# v1_0.net
KiCad netlist of a schematic drawn in Altium Designer
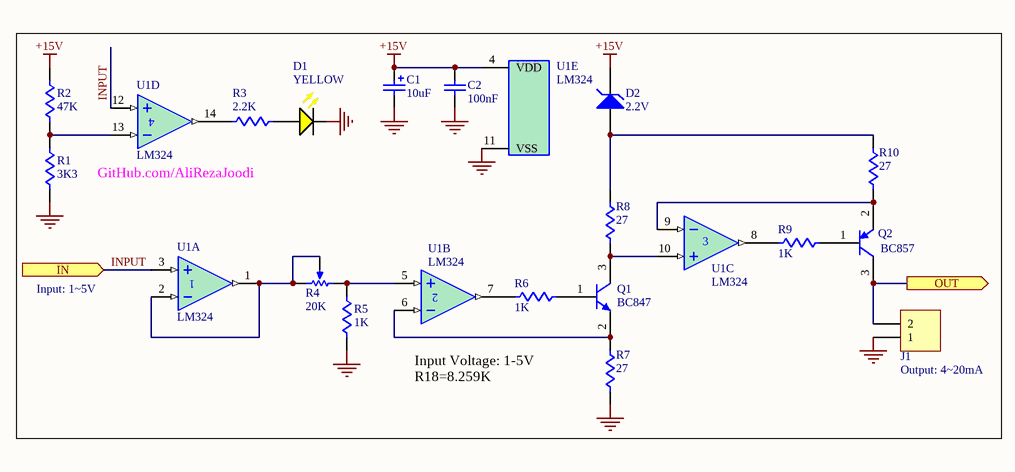
[diagram p0: v1.0.SchDoc]

(export (version "E")
  (design (tool "Eeschema 10.0.6"))
  (components
    (comp (ref "C1")
      (value "10uF")
      (footprint "Cap_B")
      (description "Polarized Capacitor (Radial)")
      (fields
        (field (name "MANUFACTURER") "Generic Components")
        (field (name "Comment") "Capacitor")
        (field (name "PUBLISHER") "Altium Limited")
      )
      (libsource (lib "Miscellaneous Devices") (part "Cap Pol1"))
    )
    (comp (ref "C2")
      (value "100nF")
      (footprint "0805")
      (description "Capacitor")
      (fields
        (field (name "MANUFACTURER") "Generic Components")
        (field (name "Comment") "Cap")
        (field (name "PUBLISHER") "Altium Limited")
      )
      (libsource (lib "Miscellaneous Devices") (part "Cap"))
    )
    (comp (ref "D1")
      (value "YELLOW")
      (footprint "LED_THD_3MM_YELLOW_R")
      (description "LED, Yellow")
      (fields (field (name "MANUFACTURER") "Generic Components") (field (name "PUBLISHER") "Altium Limited"))
      (libsource (lib "Display") (part "LED_YELLOW"))
    )
    (comp (ref "D2")
      (value "2.2V")
      (footprint "MELF-D3516-1406")
      (description "Zener Diode")
      (fields
        (field (name "MANUFACTURER") "Generic Components")
        (field (name "Comment") "LED")
        (field (name "PUBLISHER") "Altium Limited")
      )
      (libsource (lib "Miscellaneous Devices") (part "D Zener"))
    )
    (comp (ref "J1")
      (value "J17")
      (footprint "Fonics_2PIN_1")
      (description "Header, 2-Pin")
      (fields (field (name "PUBLISHER") "Altium Limited"))
      (libsource (lib "Miscellaneous Connectors") (part "Header 2"))
    )
    (comp (ref "Q1")
      (value "BC847")
      (footprint "SOT23-3N")
      (description "Silicon Bipolar Transistor")
      (fields (field (name "Comment") "NPN"))
      (libsource (lib "my Libraries") (part "BC847"))
    )
    (comp (ref "Q2")
      (value "BC857")
      (footprint "SOT23-3N")
      (description "Silicon Bipolar Transistor")
      (fields (field (name "Comment") "Q"))
      (libsource (lib "my Libraries") (part "BC857"))
    )
    (comp (ref "R1")
      (value "3K3")
      (footprint "0805")
      (description "Resistor")
      (fields (field (name "MANUFACTURER") "Generic Components") (field (name "PUBLISHER") "Altium Limited"))
      (libsource (lib "Miscellaneous Devices") (part "Res1"))
    )
    (comp (ref "R2")
      (value "47K")
      (footprint "0805")
      (description "Resistor")
      (fields
        (field (name "MANUFACTURER") "Generic Components")
        (field (name "Comment") "Res")
        (field (name "PUBLISHER") "Altium Limited")
      )
      (libsource (lib "Miscellaneous Devices") (part "Res1"))
    )
    (comp (ref "R3")
      (value "2.2K")
      (footprint "0805")
      (description "Resistor")
      (fields
        (field (name "MANUFACTURER") "Generic Components")
        (field (name "Comment") "Res")
        (field (name "PUBLISHER") "Altium Limited")
      )
      (libsource (lib "Miscellaneous Devices") (part "Res1"))
    )
    (comp (ref "R4")
      (value "20K")
      (footprint "VR4_")
      (description "Potentiometer")
      (fields
        (field (name "MANUFACTURER") "Generic Components")
        (field (name "Comment") "RES")
        (field (name "PUBLISHER") "Altium Limited")
      )
      (libsource (lib "my Libraries") (part "RPot1"))
    )
    (comp (ref "R5")
      (value "1K")
      (footprint "0805")
      (description "Resistor")
      (fields
        (field (name "MANUFACTURER") "Generic Components")
        (field (name "Comment") "RES")
        (field (name "PUBLISHER") "Altium Limited")
      )
      (libsource (lib "Miscellaneous Devices") (part "Res1"))
    )
    (comp (ref "R6")
      (value "1K")
      (footprint "0805")
      (description "Resistor")
      (fields
        (field (name "MANUFACTURER") "Generic Components")
        (field (name "Comment") "RES")
        (field (name "PUBLISHER") "Altium Limited")
      )
      (libsource (lib "Miscellaneous Devices") (part "Res1"))
    )
    (comp (ref "R7")
      (value "27")
      (footprint "0805")
      (description "Resistor")
      (fields
        (field (name "MANUFACTURER") "Generic Components")
        (field (name "Comment") "R59")
        (field (name "PUBLISHER") "Altium Limited")
      )
      (libsource (lib "Miscellaneous Devices") (part "Res1"))
    )
    (comp (ref "R8")
      (value "27")
      (footprint "0805")
      (description "Resistor")
      (fields
        (field (name "MANUFACTURER") "Generic Components")
        (field (name "Comment") "R58")
        (field (name "PUBLISHER") "Altium Limited")
      )
      (libsource (lib "Miscellaneous Devices") (part "Res1"))
    )
    (comp (ref "R9")
      (value "1K")
      (footprint "0805")
      (description "Resistor")
      (fields
        (field (name "MANUFACTURER") "Generic Components")
        (field (name "Comment") "R61")
        (field (name "PUBLISHER") "Altium Limited")
      )
      (libsource (lib "Miscellaneous Devices") (part "Res1"))
    )
    (comp (ref "R10")
      (value "27")
      (footprint "0805")
      (description "Resistor")
      (fields
        (field (name "MANUFACTURER") "Generic Components")
        (field (name "Comment") "R60")
        (field (name "PUBLISHER") "Altium Limited")
      )
      (libsource (lib "Miscellaneous Devices") (part "Res1"))
    )
    (comp (ref "U1")
      (value "LM324")
      (footprint "DIP_14")
      (description "Quad Low-Power Operational Amplifier")
      (fields (field (name "PUBLISHER") "Altium Limited"))
      (libsource (lib "Op-Amp") (part "LM324"))
    )
  )
  (nets
    (net (code "1") (name "+15V") (class "Default")
      (node (ref "C1") (pin "1") (pinfunction "1_1") (pintype "passive"))
      (node (ref "C2") (pin "2") (pinfunction "2_2") (pintype "passive"))
      (node (ref "D2") (pin "2") (pinfunction "K_2") (pintype "passive"))
      (node (ref "R2") (pin "1") (pinfunction "1_1") (pintype "passive"))
      (node (ref "U1") (pin "4") (pinfunction "VDD_4") (pintype "passive"))
    )
    (net (code "2") (name "/INPUT") (class "Default")
      (node (ref "U1") (pin "12") (pinfunction "IN+_12") (pintype "input"))
      (node (ref "U1") (pin "3") (pinfunction "IN+_3") (pintype "input"))
    )
    (net (code "3") (name "/OUT") (class "Default")
      (node (ref "J1") (pin "2") (pinfunction "2_2") (pintype "passive"))
      (node (ref "Q2") (pin "3") (pinfunction "C_3") (pintype "passive"))
    )
    (net (code "4") (name "GND") (class "Default")
      (node (ref "C1") (pin "2") (pinfunction "2_2") (pintype "passive"))
      (node (ref "C2") (pin "1") (pinfunction "1_1") (pintype "passive"))
      (node (ref "D1") (pin "2") (pinfunction "K_2") (pintype "passive"))
      (node (ref "J1") (pin "1") (pinfunction "1_1") (pintype "passive"))
      (node (ref "R1") (pin "2") (pinfunction "2_2") (pintype "passive"))
      (node (ref "R5") (pin "2") (pinfunction "2_2") (pintype "passive"))
      (node (ref "R7") (pin "1") (pinfunction "1_1") (pintype "passive"))
      (node (ref "U1") (pin "11") (pinfunction "VSS_11") (pintype "power_in"))
    )
    (net (code "5") (name "Net-(D1-A)") (class "Default")
      (node (ref "D1") (pin "1") (pinfunction "A_1") (pintype "passive"))
      (node (ref "R3") (pin "1") (pinfunction "1_1") (pintype "passive"))
    )
    (net (code "6") (name "Net-(D2-A)") (class "Default")
      (node (ref "D2") (pin "1") (pinfunction "A_1") (pintype "passive"))
      (node (ref "R10") (pin "2") (pinfunction "2_2") (pintype "passive"))
      (node (ref "R8") (pin "2") (pinfunction "2_2") (pintype "passive"))
    )
    (net (code "7") (name "Net-(Q1-B)") (class "Default")
      (node (ref "Q1") (pin "1") (pinfunction "B_1") (pintype "passive"))
      (node (ref "R6") (pin "2") (pinfunction "2_2") (pintype "passive"))
    )
    (net (code "8") (name "Net-(Q1-C)") (class "Default")
      (node (ref "Q1") (pin "3") (pinfunction "C_3") (pintype "passive"))
      (node (ref "R8") (pin "1") (pinfunction "1_1") (pintype "passive"))
      (node (ref "U1") (pin "10") (pinfunction "IN+_10") (pintype "input"))
    )
    (net (code "9") (name "Net-(Q1-E)") (class "Default")
      (node (ref "Q1") (pin "2") (pinfunction "E_2") (pintype "passive"))
      (node (ref "R7") (pin "2") (pinfunction "2_2") (pintype "passive"))
      (node (ref "U1") (pin "6") (pinfunction "IN-_6") (pintype "input"))
    )
    (net (code "10") (name "Net-(Q2-B)") (class "Default")
      (node (ref "Q2") (pin "1") (pinfunction "B_1") (pintype "passive"))
      (node (ref "R9") (pin "2") (pinfunction "2_2") (pintype "passive"))
    )
    (net (code "11") (name "Net-(Q2-E)") (class "Default")
      (node (ref "Q2") (pin "2") (pinfunction "E_2") (pintype "passive"))
      (node (ref "R10") (pin "1") (pinfunction "1_1") (pintype "passive"))
      (node (ref "U1") (pin "9") (pinfunction "IN-_9") (pintype "input"))
    )
    (net (code "12") (name "Net-(R4-BOT)") (class "Default")
      (node (ref "R4") (pin "2") (pinfunction "BOT_2") (pintype "passive"))
      (node (ref "R4") (pin "3") (pinfunction "TAP_3") (pintype "passive"))
      (node (ref "U1") (pin "1") (pinfunction "OUT_1") (pintype "output"))
      (node (ref "U1") (pin "2") (pinfunction "IN-_2") (pintype "input"))
    )
    (net (code "13") (name "Net-(R4-TOP)") (class "Default")
      (node (ref "R4") (pin "1") (pinfunction "TOP_1") (pintype "passive"))
      (node (ref "R5") (pin "1") (pinfunction "1_1") (pintype "passive"))
      (node (ref "U1") (pin "5") (pinfunction "IN+_5") (pintype "input"))
    )
    (net (code "14") (name "Net-(U1B-OUT)") (class "Default")
      (node (ref "R6") (pin "1") (pinfunction "1_1") (pintype "passive"))
      (node (ref "U1") (pin "7") (pinfunction "OUT_7") (pintype "output"))
    )
    (net (code "15") (name "Net-(U1C-OUT)") (class "Default")
      (node (ref "R9") (pin "1") (pinfunction "1_1") (pintype "passive"))
      (node (ref "U1") (pin "8") (pinfunction "OUT_8") (pintype "output"))
    )
    (net (code "16") (name "Net-(U1D-IN-)") (class "Default")
      (node (ref "R1") (pin "1") (pinfunction "1_1") (pintype "passive"))
      (node (ref "R2") (pin "2") (pinfunction "2_2") (pintype "passive"))
      (node (ref "U1") (pin "13") (pinfunction "IN-_13") (pintype "input"))
    )
    (net (code "17") (name "Net-(U1D-OUT)") (class "Default")
      (node (ref "R3") (pin "2") (pinfunction "2_2") (pintype "passive"))
      (node (ref "U1") (pin "14") (pinfunction "OUT_14") (pintype "output"))
    )
  )
)
